# main.net
KiCad netlist of a schematic drawn in EAGLE
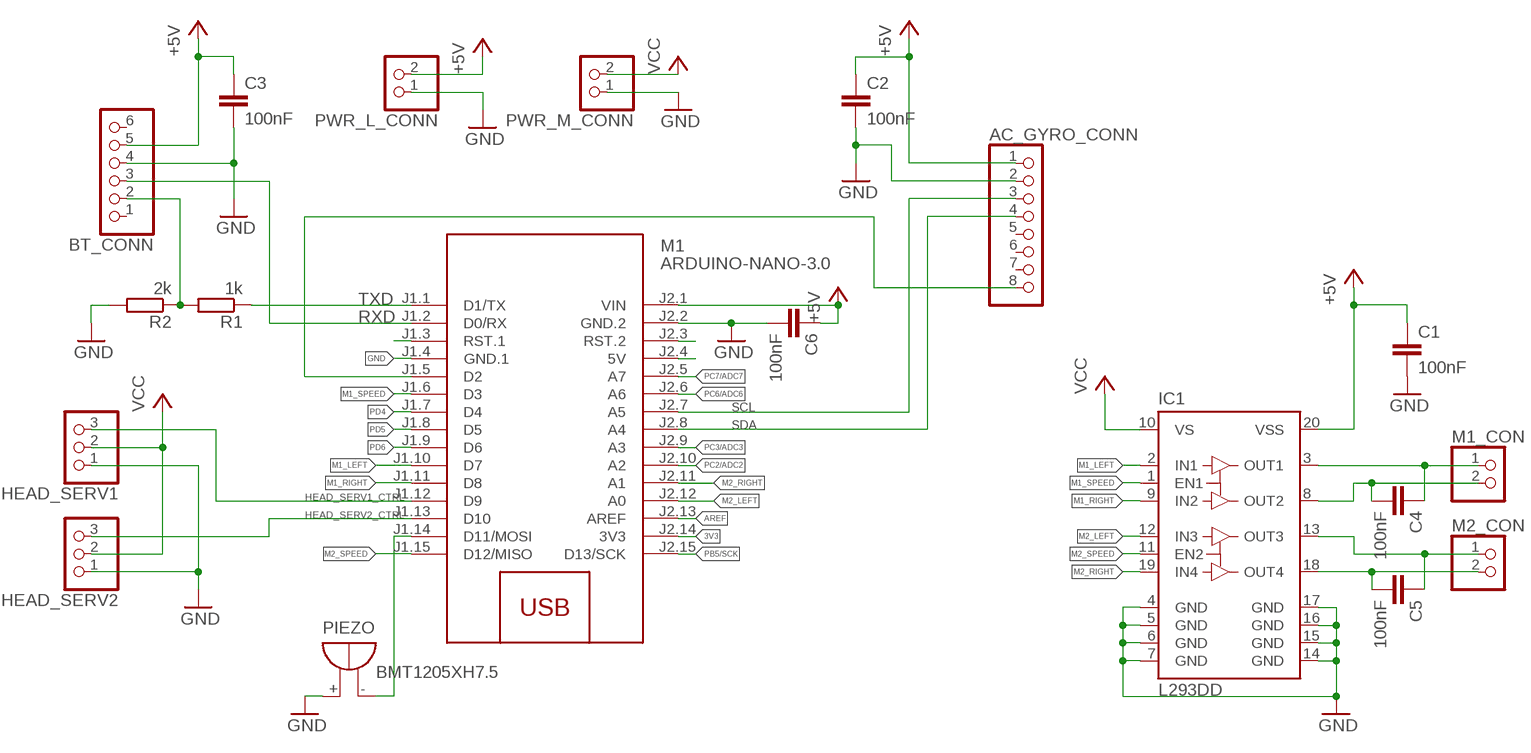
[diagram p0: schematic, sheet 1]

(export (version "E")
  (design (tool "Eeschema 10.0.6"))
  (components
    (comp (ref "AC_GYRO_CONN")
      (value "PINHD-1X8")
      (footprint "eagle-import:1X08")
      (libsource (lib "eagle-import") (part "PINHD-1X8"))
    )
    (comp (ref "BT_CONN")
      (value "PINHD-1X6")
      (footprint "eagle-import:1X06")
      (libsource (lib "eagle-import") (part "PINHD-1X6"))
    )
    (comp (ref "C1")
      (value "100nF")
      (footprint "eagle-import:C0805")
      (libsource (lib "eagle-import") (part "C-EUC0805"))
    )
    (comp (ref "C2")
      (value "100nF")
      (footprint "eagle-import:C0805")
      (libsource (lib "eagle-import") (part "C-EUC0805"))
    )
    (comp (ref "C3")
      (value "100nF")
      (footprint "eagle-import:C0805")
      (libsource (lib "eagle-import") (part "C-EUC0805"))
    )
    (comp (ref "C4")
      (value "100nF")
      (footprint "eagle-import:C0805")
      (libsource (lib "eagle-import") (part "C-EUC0805"))
    )
    (comp (ref "C5")
      (value "100nF")
      (footprint "eagle-import:C0805")
      (libsource (lib "eagle-import") (part "C-EUC0805"))
    )
    (comp (ref "C6")
      (value "100nF")
      (footprint "eagle-import:C0805")
      (libsource (lib "eagle-import") (part "C-EUC0805"))
    )
    (comp (ref "HEAD_SERV1")
      (value "PINHD-1X3")
      (footprint "eagle-import:1X03")
      (libsource (lib "eagle-import") (part "PINHD-1X3"))
    )
    (comp (ref "HEAD_SERV2")
      (value "PINHD-1X3")
      (footprint "eagle-import:1X03")
      (libsource (lib "eagle-import") (part "PINHD-1X3"))
    )
    (comp (ref "IC1")
      (value "L293DD")
      (footprint "eagle-import:SO20")
      (libsource (lib "eagle-import") (part "L293DD"))
    )
    (comp (ref "M1")
      (value "ARDUINO-NANO-3.0")
      (footprint "eagle-import:ARDUINO-NANO-3.0")
      (libsource (lib "eagle-import") (part "ARDUINO-NANO-3.0"))
    )
    (comp (ref "M1_CON")
      (value "PINHD-1X2")
      (footprint "eagle-import:1X02")
      (libsource (lib "eagle-import") (part "PINHD-1X2"))
    )
    (comp (ref "M2_CON")
      (value "PINHD-1X2")
      (footprint "eagle-import:1X02")
      (libsource (lib "eagle-import") (part "PINHD-1X2"))
    )
    (comp (ref "PIEZO")
      (value "BMT1205XH7.5")
      (footprint "eagle-import:BMT1205XH7.5")
      (libsource (lib "eagle-import") (part "BMT1205XH7.5"))
    )
    (comp (ref "PWR_L_CONN")
      (value "PINHD-1X2")
      (footprint "eagle-import:1X02")
      (libsource (lib "eagle-import") (part "PINHD-1X2"))
    )
    (comp (ref "PWR_M_CONN")
      (value "PINHD-1X2")
      (footprint "eagle-import:1X02")
      (libsource (lib "eagle-import") (part "PINHD-1X2"))
    )
    (comp (ref "R1")
      (value "1k")
      (footprint "eagle-import:0207_10")
      (libsource (lib "eagle-import") (part "R-EU_0207/10"))
    )
    (comp (ref "R2")
      (value "2k")
      (footprint "eagle-import:0207_10")
      (libsource (lib "eagle-import") (part "R-EU_0207/10"))
    )
  )
  (nets
    (net (code "1") (name "+5V") (class "Default")
      (node (ref "AC_GYRO_CONN") (pin "1") (pinfunction "1_1") (pintype "passive"))
      (node (ref "BT_CONN") (pin "5") (pinfunction "5_5") (pintype "passive"))
      (node (ref "C1") (pin "1") (pinfunction "1_1") (pintype "passive"))
      (node (ref "C2") (pin "1") (pinfunction "1_1") (pintype "passive"))
      (node (ref "C3") (pin "1") (pinfunction "1_1") (pintype "passive"))
      (node (ref "C6") (pin "1") (pinfunction "1_1") (pintype "passive"))
      (node (ref "IC1") (pin "20") (pinfunction "VSS_20") (pintype "power_in"))
      (node (ref "M1") (pin "J2.1") (pinfunction "VIN_J2.1") (pintype "power_in"))
      (node (ref "PWR_L_CONN") (pin "2") (pinfunction "2_2") (pintype "passive"))
    )
    (net (code "2") (name "/HEAD_SERV1_CTRL") (class "Default")
      (node (ref "HEAD_SERV1") (pin "3") (pinfunction "3_3") (pintype "passive"))
      (node (ref "M1") (pin "J1.12") (pinfunction "D9_J1.12") (pintype "bidirectional"))
    )
    (net (code "3") (name "/HEAD_SERV2_CTRL") (class "Default")
      (node (ref "HEAD_SERV2") (pin "3") (pinfunction "3_3") (pintype "passive"))
      (node (ref "M1") (pin "J1.13") (pinfunction "D10_J1.13") (pintype "bidirectional"))
    )
    (net (code "4") (name "/RXD") (class "Default")
      (node (ref "BT_CONN") (pin "3") (pinfunction "3_3") (pintype "passive"))
      (node (ref "M1") (pin "J1.2") (pinfunction "D0/RX_J1.2") (pintype "bidirectional"))
    )
    (net (code "5") (name "/SCL") (class "Default")
      (node (ref "AC_GYRO_CONN") (pin "3") (pinfunction "3_3") (pintype "passive"))
      (node (ref "M1") (pin "J2.7") (pinfunction "A5_J2.7") (pintype "bidirectional"))
    )
    (net (code "6") (name "/SDA") (class "Default")
      (node (ref "AC_GYRO_CONN") (pin "4") (pinfunction "4_4") (pintype "passive"))
      (node (ref "M1") (pin "J2.8") (pinfunction "A4_J2.8") (pintype "bidirectional"))
    )
    (net (code "7") (name "/TXD") (class "Default")
      (node (ref "M1") (pin "J1.1") (pinfunction "D1/TX_J1.1") (pintype "bidirectional"))
      (node (ref "R1") (pin "1") (pinfunction "1_1") (pintype "passive"))
    )
    (net (code "8") (name "3V3") (class "Default")
      (node (ref "M1") (pin "J2.14") (pinfunction "3V3_J2.14") (pintype "power_in"))
    )
    (net (code "9") (name "AREF") (class "Default")
      (node (ref "M1") (pin "J2.13") (pinfunction "AREF_J2.13") (pintype "bidirectional"))
    )
    (net (code "10") (name "GND") (class "Default")
      (node (ref "AC_GYRO_CONN") (pin "2") (pinfunction "2_2") (pintype "passive"))
      (node (ref "BT_CONN") (pin "4") (pinfunction "4_4") (pintype "passive"))
      (node (ref "C1") (pin "2") (pinfunction "2_2") (pintype "passive"))
      (node (ref "C2") (pin "2") (pinfunction "2_2") (pintype "passive"))
      (node (ref "C3") (pin "2") (pinfunction "2_2") (pintype "passive"))
      (node (ref "C6") (pin "2") (pinfunction "2_2") (pintype "passive"))
      (node (ref "HEAD_SERV1") (pin "1") (pinfunction "1_1") (pintype "passive"))
      (node (ref "HEAD_SERV2") (pin "1") (pinfunction "1_1") (pintype "passive"))
      (node (ref "IC1") (pin "14") (pinfunction "GND_14") (pintype "power_in"))
      (node (ref "IC1") (pin "15") (pinfunction "GND_15") (pintype "power_in"))
      (node (ref "IC1") (pin "16") (pinfunction "GND_16") (pintype "power_in"))
      (node (ref "IC1") (pin "17") (pinfunction "GND_17") (pintype "power_in"))
      (node (ref "IC1") (pin "4") (pinfunction "GND_4") (pintype "power_in"))
      (node (ref "IC1") (pin "5") (pinfunction "GND_5") (pintype "power_in"))
      (node (ref "IC1") (pin "6") (pinfunction "GND_6") (pintype "power_in"))
      (node (ref "IC1") (pin "7") (pinfunction "GND_7") (pintype "power_in"))
      (node (ref "M1") (pin "J1.4") (pinfunction "GND.1_J1.4") (pintype "power_in"))
      (node (ref "M1") (pin "J2.2") (pinfunction "GND.2_J2.2") (pintype "power_in"))
      (node (ref "PIEZO") (pin "+") (pinfunction "+_+") (pintype "passive"))
      (node (ref "PWR_L_CONN") (pin "1") (pinfunction "1_1") (pintype "passive"))
      (node (ref "PWR_M_CONN") (pin "1") (pinfunction "1_1") (pintype "passive"))
      (node (ref "R2") (pin "2") (pinfunction "2_2") (pintype "passive"))
    )
    (net (code "11") (name "M1_LEFT") (class "Default")
      (node (ref "IC1") (pin "2") (pinfunction "IN1_2") (pintype "input"))
      (node (ref "M1") (pin "J1.10") (pinfunction "D7_J1.10") (pintype "bidirectional"))
    )
    (net (code "12") (name "M1_RIGHT") (class "Default")
      (node (ref "IC1") (pin "9") (pinfunction "IN2_9") (pintype "input"))
      (node (ref "M1") (pin "J1.11") (pinfunction "D8_J1.11") (pintype "bidirectional"))
    )
    (net (code "13") (name "M1_SPEED") (class "Default")
      (node (ref "IC1") (pin "1") (pinfunction "EN1_1") (pintype "input"))
      (node (ref "M1") (pin "J1.6") (pinfunction "D3_J1.6") (pintype "bidirectional"))
    )
    (net (code "14") (name "M2_LEFT") (class "Default")
      (node (ref "IC1") (pin "12") (pinfunction "IN3_12") (pintype "input"))
      (node (ref "M1") (pin "J2.12") (pinfunction "A0_J2.12") (pintype "bidirectional"))
    )
    (net (code "15") (name "M2_RIGHT") (class "Default")
      (node (ref "IC1") (pin "19") (pinfunction "IN4_19") (pintype "input"))
      (node (ref "M1") (pin "J2.11") (pinfunction "A1_J2.11") (pintype "bidirectional"))
    )
    (net (code "16") (name "M2_SPEED") (class "Default")
      (node (ref "IC1") (pin "11") (pinfunction "EN2_11") (pintype "input"))
      (node (ref "M1") (pin "J1.15") (pinfunction "D12/MISO_J1.15") (pintype "bidirectional"))
    )
    (net (code "17") (name "Net-(BT_CONN-Pad2)") (class "Default")
      (node (ref "BT_CONN") (pin "2") (pinfunction "2_2") (pintype "passive"))
      (node (ref "R1") (pin "2") (pinfunction "2_2") (pintype "passive"))
      (node (ref "R2") (pin "1") (pinfunction "1_1") (pintype "passive"))
    )
    (net (code "18") (name "Net-(IC1-OUT1)") (class "Default")
      (node (ref "C4") (pin "1") (pinfunction "1_1") (pintype "passive"))
      (node (ref "IC1") (pin "3") (pinfunction "OUT1_3") (pintype "output"))
      (node (ref "M1_CON") (pin "1") (pinfunction "1_1") (pintype "passive"))
    )
    (net (code "19") (name "Net-(IC1-OUT2)") (class "Default")
      (node (ref "C4") (pin "2") (pinfunction "2_2") (pintype "passive"))
      (node (ref "IC1") (pin "8") (pinfunction "OUT2_8") (pintype "output"))
      (node (ref "M1_CON") (pin "2") (pinfunction "2_2") (pintype "passive"))
    )
    (net (code "20") (name "Net-(IC1-OUT3)") (class "Default")
      (node (ref "C5") (pin "1") (pinfunction "1_1") (pintype "passive"))
      (node (ref "IC1") (pin "13") (pinfunction "OUT3_13") (pintype "output"))
      (node (ref "M2_CON") (pin "1") (pinfunction "1_1") (pintype "passive"))
    )
    (net (code "21") (name "Net-(IC1-OUT4)") (class "Default")
      (node (ref "C5") (pin "2") (pinfunction "2_2") (pintype "passive"))
      (node (ref "IC1") (pin "18") (pinfunction "OUT4_18") (pintype "output"))
      (node (ref "M2_CON") (pin "2") (pinfunction "2_2") (pintype "passive"))
    )
    (net (code "22") (name "Net-(M1-D2)") (class "Default")
      (node (ref "AC_GYRO_CONN") (pin "8") (pinfunction "8_8") (pintype "passive"))
      (node (ref "M1") (pin "J1.5") (pinfunction "D2_J1.5") (pintype "bidirectional"))
    )
    (net (code "23") (name "Net-(M1-D11{slash}MOSI)") (class "Default")
      (node (ref "M1") (pin "J1.14") (pinfunction "D11/MOSI_J1.14") (pintype "bidirectional"))
      (node (ref "PIEZO") (pin "-") (pinfunction "-_-") (pintype "passive"))
    )
    (net (code "24") (name "PB5{slash}SCK") (class "Default")
      (node (ref "M1") (pin "J2.15") (pinfunction "D13/SCK_J2.15") (pintype "bidirectional"))
    )
    (net (code "25") (name "PC2{slash}ADC2") (class "Default")
      (node (ref "M1") (pin "J2.10") (pinfunction "A2_J2.10") (pintype "bidirectional"))
    )
    (net (code "26") (name "PC3{slash}ADC3") (class "Default")
      (node (ref "M1") (pin "J2.9") (pinfunction "A3_J2.9") (pintype "bidirectional"))
    )
    (net (code "27") (name "PC6{slash}ADC6") (class "Default")
      (node (ref "M1") (pin "J2.6") (pinfunction "A6_J2.6") (pintype "bidirectional"))
    )
    (net (code "28") (name "PC7{slash}ADC7") (class "Default")
      (node (ref "M1") (pin "J2.5") (pinfunction "A7_J2.5") (pintype "bidirectional"))
    )
    (net (code "29") (name "PD4") (class "Default")
      (node (ref "M1") (pin "J1.7") (pinfunction "D4_J1.7") (pintype "bidirectional"))
    )
    (net (code "30") (name "PD5") (class "Default")
      (node (ref "M1") (pin "J1.8") (pinfunction "D5_J1.8") (pintype "bidirectional"))
    )
    (net (code "31") (name "PD6") (class "Default")
      (node (ref "M1") (pin "J1.9") (pinfunction "D6_J1.9") (pintype "bidirectional"))
    )
    (net (code "32") (name "VCC") (class "Default")
      (node (ref "HEAD_SERV1") (pin "2") (pinfunction "2_2") (pintype "passive"))
      (node (ref "HEAD_SERV2") (pin "2") (pinfunction "2_2") (pintype "passive"))
      (node (ref "IC1") (pin "10") (pinfunction "VS_10") (pintype "power_in"))
      (node (ref "PWR_M_CONN") (pin "2") (pinfunction "2_2") (pintype "passive"))
    )
    (net (code "33") (name "unconnected-(AC_GYRO_CONN-Pad5)") (class "Default")
      (node (ref "AC_GYRO_CONN") (pin "5") (pinfunction "5_5") (pintype "passive"))
    )
    (net (code "34") (name "unconnected-(AC_GYRO_CONN-Pad6)") (class "Default")
      (node (ref "AC_GYRO_CONN") (pin "6") (pinfunction "6_6") (pintype "passive"))
    )
    (net (code "35") (name "unconnected-(AC_GYRO_CONN-Pad7)") (class "Default")
      (node (ref "AC_GYRO_CONN") (pin "7") (pinfunction "7_7") (pintype "passive"))
    )
    (net (code "36") (name "unconnected-(BT_CONN-Pad1)") (class "Default")
      (node (ref "BT_CONN") (pin "1") (pinfunction "1_1") (pintype "passive"))
    )
    (net (code "37") (name "unconnected-(BT_CONN-Pad6)") (class "Default")
      (node (ref "BT_CONN") (pin "6") (pinfunction "6_6") (pintype "passive"))
    )
    (net (code "38") (name "unconnected-(M1-5V-PadJ2.4)") (class "Default")
      (node (ref "M1") (pin "J2.4") (pinfunction "5V_J2.4") (pintype "power_in"))
    )
    (net (code "39") (name "unconnected-(M1-RST.1-PadJ1.3)") (class "Default")
      (node (ref "M1") (pin "J1.3") (pinfunction "RST.1_J1.3") (pintype "bidirectional"))
    )
    (net (code "40") (name "unconnected-(M1-RST.2-PadJ2.3)") (class "Default")
      (node (ref "M1") (pin "J2.3") (pinfunction "RST.2_J2.3") (pintype "bidirectional"))
    )
  )
)
